# Rocket3RTC.net
KiCad netlist of a schematic drawn in EAGLE
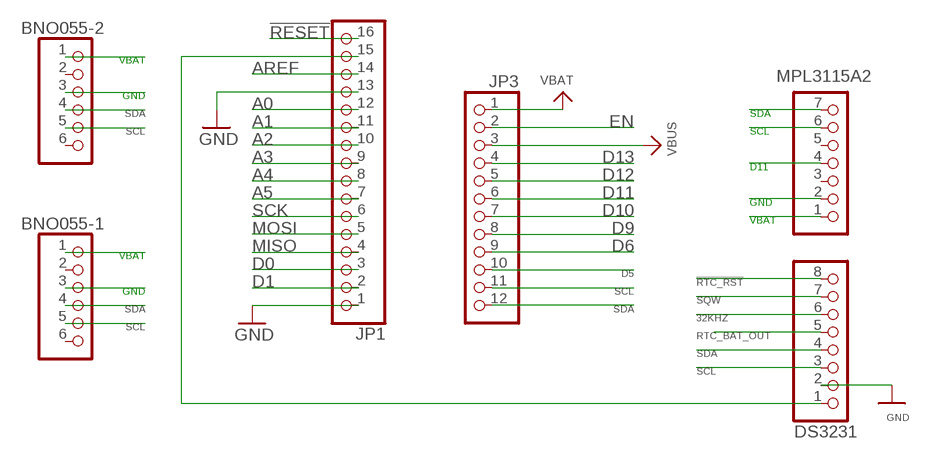
[diagram p0: schematic, sheet 1]

(export (version "E")
  (design (tool "Eeschema 10.0.6"))
  (components
    (comp (ref "BNO055-1")
      (value "HEADER-1X670MIL")
      (footprint "eagle-import:1X06_ROUND_70")
      (libsource (lib "eagle-import") (part "HEADER-1X670MIL"))
    )
    (comp (ref "BNO055-2")
      (value "HEADER-1X670MIL")
      (footprint "eagle-import:1X06_ROUND_70")
      (libsource (lib "eagle-import") (part "HEADER-1X670MIL"))
    )
    (comp (ref "DS3231")
      (value "HEADER-1X870MIL")
      (footprint "eagle-import:1X08_ROUND_70")
      (libsource (lib "eagle-import") (part "HEADER-1X870MIL"))
    )
    (comp (ref "JP1")
      (value "HEADER-1X16ROUND")
      (footprint "eagle-import:1X16_ROUND")
      (libsource (lib "eagle-import") (part "HEADER-1X16ROUND"))
    )
    (comp (ref "JP3")
      (value "HEADER-1X12")
      (footprint "eagle-import:1X12_ROUND")
      (libsource (lib "eagle-import") (part "HEADER-1X12"))
    )
    (comp (ref "MPL3115A2")
      (value "HEADER-1X770MIL")
      (footprint "eagle-import:1X07_ROUND_70")
      (libsource (lib "eagle-import") (part "HEADER-1X770MIL"))
    )
  )
  (nets
    (net (code "1") (name "/32KHZ") (class "Default")
      (node (ref "DS3231") (pin "6") (pinfunction "6_6") (pintype "passive"))
    )
    (net (code "2") (name "/A0") (class "Default")
      (node (ref "JP1") (pin "12") (pinfunction "12_12") (pintype "passive"))
    )
    (net (code "3") (name "/A1") (class "Default")
      (node (ref "JP1") (pin "11") (pinfunction "11_11") (pintype "passive"))
    )
    (net (code "4") (name "/A2") (class "Default")
      (node (ref "JP1") (pin "10") (pinfunction "10_10") (pintype "passive"))
    )
    (net (code "5") (name "/A3") (class "Default")
      (node (ref "JP1") (pin "9") (pinfunction "9_9") (pintype "passive"))
    )
    (net (code "6") (name "/A4") (class "Default")
      (node (ref "JP1") (pin "8") (pinfunction "8_8") (pintype "passive"))
    )
    (net (code "7") (name "/A5") (class "Default")
      (node (ref "JP1") (pin "7") (pinfunction "7_7") (pintype "passive"))
    )
    (net (code "8") (name "/AREF") (class "Default")
      (node (ref "JP1") (pin "14") (pinfunction "14_14") (pintype "passive"))
    )
    (net (code "9") (name "/D0") (class "Default")
      (node (ref "JP1") (pin "3") (pinfunction "3_3") (pintype "passive"))
    )
    (net (code "10") (name "/D1") (class "Default")
      (node (ref "JP1") (pin "2") (pinfunction "2_2") (pintype "passive"))
    )
    (net (code "11") (name "/D5") (class "Default")
      (node (ref "JP3") (pin "10") (pinfunction "10_10") (pintype "passive"))
    )
    (net (code "12") (name "/D6") (class "Default")
      (node (ref "JP3") (pin "9") (pinfunction "9_9") (pintype "passive"))
    )
    (net (code "13") (name "/D9") (class "Default")
      (node (ref "JP3") (pin "8") (pinfunction "8_8") (pintype "passive"))
    )
    (net (code "14") (name "/D10") (class "Default")
      (node (ref "JP3") (pin "7") (pinfunction "7_7") (pintype "passive"))
    )
    (net (code "15") (name "/D11") (class "Default")
      (node (ref "JP3") (pin "6") (pinfunction "6_6") (pintype "passive"))
      (node (ref "MPL3115A2") (pin "4") (pinfunction "4_4") (pintype "passive"))
    )
    (net (code "16") (name "/D12") (class "Default")
      (node (ref "JP3") (pin "5") (pinfunction "5_5") (pintype "passive"))
    )
    (net (code "17") (name "/D13") (class "Default")
      (node (ref "JP3") (pin "4") (pinfunction "4_4") (pintype "passive"))
    )
    (net (code "18") (name "/EN") (class "Default")
      (node (ref "JP3") (pin "2") (pinfunction "2_2") (pintype "passive"))
    )
    (net (code "19") (name "/MISO") (class "Default")
      (node (ref "JP1") (pin "4") (pinfunction "4_4") (pintype "passive"))
    )
    (net (code "20") (name "/MOSI") (class "Default")
      (node (ref "JP1") (pin "5") (pinfunction "5_5") (pintype "passive"))
    )
    (net (code "21") (name "/RTC_BAT_OUT") (class "Default")
      (node (ref "DS3231") (pin "5") (pinfunction "5_5") (pintype "passive"))
    )
    (net (code "22") (name "/SCK") (class "Default")
      (node (ref "JP1") (pin "6") (pinfunction "6_6") (pintype "passive"))
    )
    (net (code "23") (name "/SCL") (class "Default")
      (node (ref "BNO055-1") (pin "5") (pinfunction "5_5") (pintype "passive"))
      (node (ref "BNO055-2") (pin "5") (pinfunction "5_5") (pintype "passive"))
      (node (ref "DS3231") (pin "3") (pinfunction "3_3") (pintype "passive"))
      (node (ref "JP3") (pin "11") (pinfunction "11_11") (pintype "passive"))
      (node (ref "MPL3115A2") (pin "6") (pinfunction "6_6") (pintype "passive"))
    )
    (net (code "24") (name "/SDA") (class "Default")
      (node (ref "BNO055-1") (pin "4") (pinfunction "4_4") (pintype "passive"))
      (node (ref "BNO055-2") (pin "4") (pinfunction "4_4") (pintype "passive"))
      (node (ref "DS3231") (pin "4") (pinfunction "4_4") (pintype "passive"))
      (node (ref "JP3") (pin "12") (pinfunction "12_12") (pintype "passive"))
      (node (ref "MPL3115A2") (pin "7") (pinfunction "7_7") (pintype "passive"))
    )
    (net (code "25") (name "/SQW") (class "Default")
      (node (ref "DS3231") (pin "7") (pinfunction "7_7") (pintype "passive"))
    )
    (net (code "26") (name "/~{RESET}") (class "Default")
      (node (ref "JP1") (pin "16") (pinfunction "16_16") (pintype "passive"))
    )
    (net (code "27") (name "/~{RTC_RST}") (class "Default")
      (node (ref "DS3231") (pin "8") (pinfunction "8_8") (pintype "passive"))
    )
    (net (code "28") (name "GND") (class "Default")
      (node (ref "BNO055-1") (pin "3") (pinfunction "3_3") (pintype "passive"))
      (node (ref "BNO055-2") (pin "3") (pinfunction "3_3") (pintype "passive"))
      (node (ref "DS3231") (pin "2") (pinfunction "2_2") (pintype "passive"))
      (node (ref "JP1") (pin "1") (pinfunction "1_1") (pintype "passive"))
      (node (ref "JP1") (pin "13") (pinfunction "13_13") (pintype "passive"))
      (node (ref "MPL3115A2") (pin "2") (pinfunction "2_2") (pintype "passive"))
    )
    (net (code "29") (name "Net-(DS3231-Pad1)") (class "Default")
      (node (ref "DS3231") (pin "1") (pinfunction "1_1") (pintype "passive"))
      (node (ref "JP1") (pin "15") (pinfunction "15_15") (pintype "passive"))
    )
    (net (code "30") (name "VBAT") (class "Default")
      (node (ref "BNO055-1") (pin "1") (pinfunction "1_1") (pintype "passive"))
      (node (ref "BNO055-2") (pin "1") (pinfunction "1_1") (pintype "passive"))
      (node (ref "JP3") (pin "1") (pinfunction "1_1") (pintype "passive"))
      (node (ref "MPL3115A2") (pin "1") (pinfunction "1_1") (pintype "passive"))
    )
    (net (code "31") (name "VBUS") (class "Default")
      (node (ref "JP3") (pin "3") (pinfunction "3_3") (pintype "passive"))
    )
    (net (code "32") (name "unconnected-(BNO055-1-Pad2)") (class "Default")
      (node (ref "BNO055-1") (pin "2") (pinfunction "2_2") (pintype "passive"))
    )
    (net (code "33") (name "unconnected-(BNO055-1-Pad6)") (class "Default")
      (node (ref "BNO055-1") (pin "6") (pinfunction "6_6") (pintype "passive"))
    )
    (net (code "34") (name "unconnected-(BNO055-2-Pad2)") (class "Default")
      (node (ref "BNO055-2") (pin "2") (pinfunction "2_2") (pintype "passive"))
    )
    (net (code "35") (name "unconnected-(BNO055-2-Pad6)") (class "Default")
      (node (ref "BNO055-2") (pin "6") (pinfunction "6_6") (pintype "passive"))
    )
    (net (code "36") (name "unconnected-(MPL3115A2-Pad3)") (class "Default")
      (node (ref "MPL3115A2") (pin "3") (pinfunction "3_3") (pintype "passive"))
    )
    (net (code "37") (name "unconnected-(MPL3115A2-Pad5)") (class "Default")
      (node (ref "MPL3115A2") (pin "5") (pinfunction "5_5") (pintype "passive"))
    )
  )
)
